# Thermocouple-board.net
KiCad netlist of a schematic drawn in EAGLE
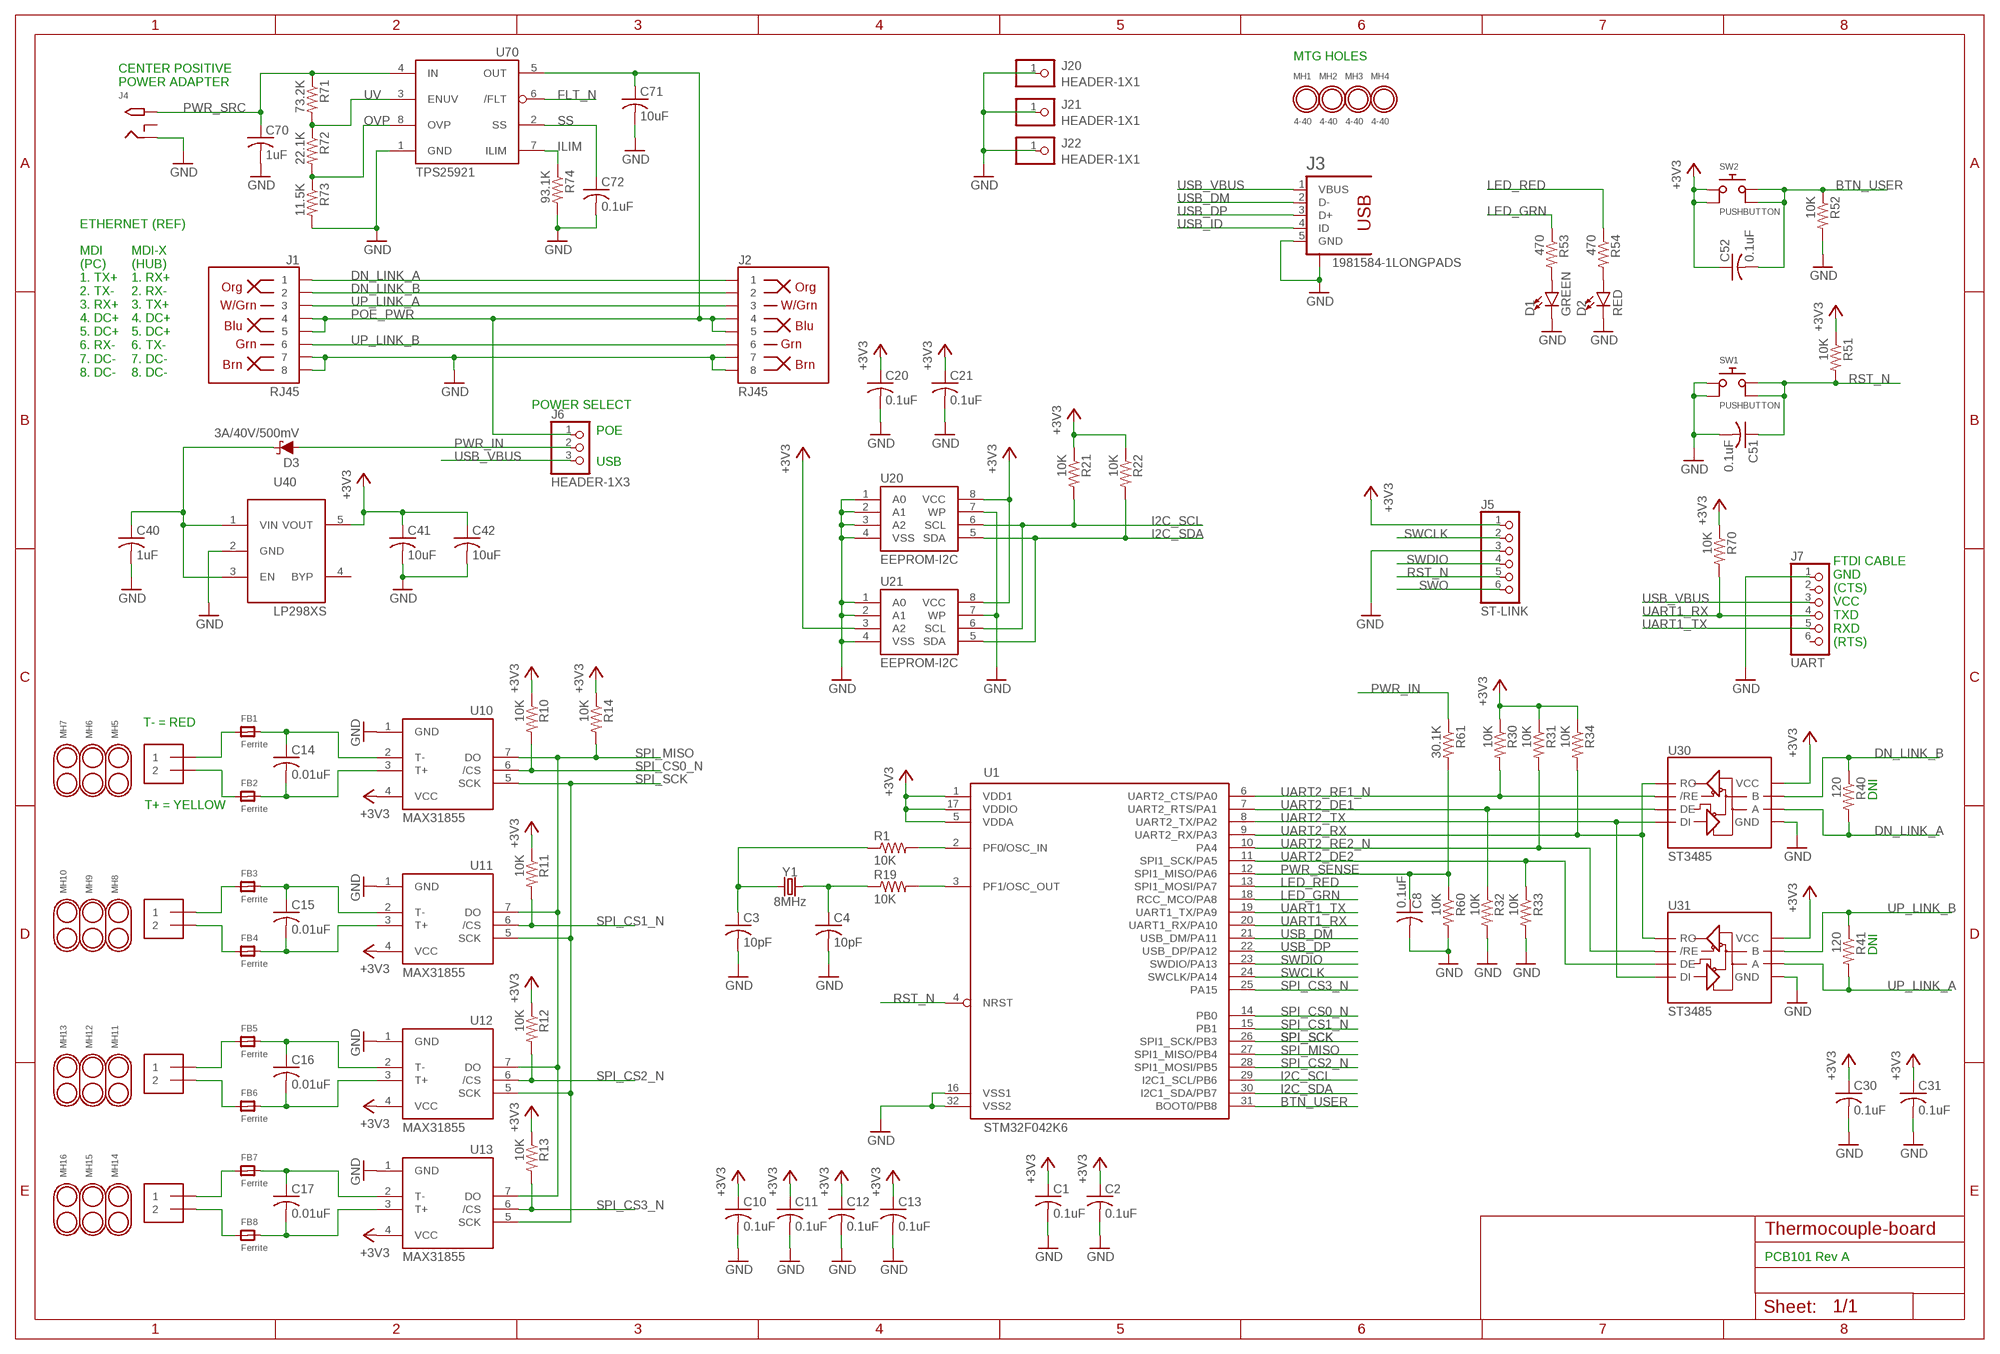
[diagram p0: schematic, sheet 1]

(export (version "E")
  (design (tool "Eeschema 10.0.6"))
  (components
    (comp (ref "C1")
      (value "0.1uF")
      (footprint "eagle-import:C0805K")
      (libsource (lib "eagle-import") (part "adafruit_420_C-USC0805K"))
    )
    (comp (ref "C2")
      (value "0.1uF")
      (footprint "eagle-import:C0805K")
      (libsource (lib "eagle-import") (part "adafruit_420_C-USC0805K"))
    )
    (comp (ref "C3")
      (value "10pF")
      (footprint "eagle-import:C0805K")
      (libsource (lib "eagle-import") (part "adafruit_420_C-USC0805K"))
    )
    (comp (ref "C4")
      (value "10pF")
      (footprint "eagle-import:C0805K")
      (libsource (lib "eagle-import") (part "adafruit_420_C-USC0805K"))
    )
    (comp (ref "C8")
      (value "0.1uF")
      (footprint "eagle-import:C0805K")
      (libsource (lib "eagle-import") (part "adafruit_420_C-USC0805K"))
    )
    (comp (ref "C10")
      (value "0.1uF")
      (footprint "eagle-import:C0805K")
      (libsource (lib "eagle-import") (part "adafruit_420_C-USC0805K"))
    )
    (comp (ref "C11")
      (value "0.1uF")
      (footprint "eagle-import:C0805K")
      (libsource (lib "eagle-import") (part "adafruit_420_C-USC0805K"))
    )
    (comp (ref "C12")
      (value "0.1uF")
      (footprint "eagle-import:C0805K")
      (libsource (lib "eagle-import") (part "adafruit_420_C-USC0805K"))
    )
    (comp (ref "C13")
      (value "0.1uF")
      (footprint "eagle-import:C0805K")
      (libsource (lib "eagle-import") (part "adafruit_420_C-USC0805K"))
    )
    (comp (ref "C14")
      (value "0.01uF")
      (footprint "eagle-import:C0805K")
      (libsource (lib "eagle-import") (part "adafruit_420_C-USC0805K"))
    )
    (comp (ref "C15")
      (value "0.01uF")
      (footprint "eagle-import:C0805K")
      (libsource (lib "eagle-import") (part "adafruit_420_C-USC0805K"))
    )
    (comp (ref "C16")
      (value "0.01uF")
      (footprint "eagle-import:C0805K")
      (libsource (lib "eagle-import") (part "adafruit_420_C-USC0805K"))
    )
    (comp (ref "C17")
      (value "0.01uF")
      (footprint "eagle-import:C0805K")
      (libsource (lib "eagle-import") (part "adafruit_420_C-USC0805K"))
    )
    (comp (ref "C20")
      (value "0.1uF")
      (footprint "eagle-import:C0805K")
      (libsource (lib "eagle-import") (part "adafruit_420_C-USC0805K"))
    )
    (comp (ref "C21")
      (value "0.1uF")
      (footprint "eagle-import:C0805K")
      (libsource (lib "eagle-import") (part "adafruit_420_C-USC0805K"))
    )
    (comp (ref "C30")
      (value "0.1uF")
      (footprint "eagle-import:C0805K")
      (libsource (lib "eagle-import") (part "adafruit_420_C-USC0805K"))
    )
    (comp (ref "C31")
      (value "0.1uF")
      (footprint "eagle-import:C0805K")
      (libsource (lib "eagle-import") (part "adafruit_420_C-USC0805K"))
    )
    (comp (ref "C40")
      (value "1uF")
      (footprint "eagle-import:C0805K")
      (libsource (lib "eagle-import") (part "C-USC0805K"))
    )
    (comp (ref "C41")
      (value "10uF")
      (footprint "eagle-import:C0805K")
      (libsource (lib "eagle-import") (part "C-USC0805K"))
    )
    (comp (ref "C42")
      (value "10uF")
      (footprint "eagle-import:C0805K")
      (libsource (lib "eagle-import") (part "C-USC0805K"))
    )
    (comp (ref "C51")
      (value "0.1uF")
      (footprint "eagle-import:C0805K")
      (libsource (lib "eagle-import") (part "adafruit_420_C-USC0805K"))
    )
    (comp (ref "C52")
      (value "0.1uF")
      (footprint "eagle-import:C0805K")
      (libsource (lib "eagle-import") (part "adafruit_420_C-USC0805K"))
    )
    (comp (ref "C70")
      (value "1uF")
      (footprint "eagle-import:C0805K")
      (libsource (lib "eagle-import") (part "adafruit_420_C-USC0805K"))
    )
    (comp (ref "C71")
      (value "10uF")
      (footprint "eagle-import:C0805K")
      (libsource (lib "eagle-import") (part "adafruit_420_C-USC0805K"))
    )
    (comp (ref "C72")
      (value "0.1uF")
      (footprint "eagle-import:C0805K")
      (libsource (lib "eagle-import") (part "adafruit_420_C-USC0805K"))
    )
    (comp (ref "D1")
      (value "GREEN")
      (footprint "eagle-import:LED-0603")
      (libsource (lib "eagle-import") (part "LED-GREEN0603"))
    )
    (comp (ref "D2")
      (value "RED")
      (footprint "eagle-import:LED-0603")
      (libsource (lib "eagle-import") (part "LED-RED0603"))
    )
    (comp (ref "D3")
      (value "3A/40V/500mV")
      (footprint "eagle-import:SMA-DIODE")
      (libsource (lib "eagle-import") (part "DIODE-SCHOTTKY-B340A"))
    )
    (comp (ref "FB1")
      (value "Ferrite")
      (footprint "eagle-import:_0805")
      (libsource (lib "eagle-import") (part "FERRITE_0805"))
    )
    (comp (ref "FB2")
      (value "Ferrite")
      (footprint "eagle-import:_0805")
      (libsource (lib "eagle-import") (part "FERRITE_0805"))
    )
    (comp (ref "FB3")
      (value "Ferrite")
      (footprint "eagle-import:_0805")
      (libsource (lib "eagle-import") (part "FERRITE_0805"))
    )
    (comp (ref "FB4")
      (value "Ferrite")
      (footprint "eagle-import:_0805")
      (libsource (lib "eagle-import") (part "FERRITE_0805"))
    )
    (comp (ref "FB5")
      (value "Ferrite")
      (footprint "eagle-import:_0805")
      (libsource (lib "eagle-import") (part "FERRITE_0805"))
    )
    (comp (ref "FB6")
      (value "Ferrite")
      (footprint "eagle-import:_0805")
      (libsource (lib "eagle-import") (part "FERRITE_0805"))
    )
    (comp (ref "FB7")
      (value "Ferrite")
      (footprint "eagle-import:_0805")
      (libsource (lib "eagle-import") (part "FERRITE_0805"))
    )
    (comp (ref "FB8")
      (value "Ferrite")
      (footprint "eagle-import:_0805")
      (libsource (lib "eagle-import") (part "FERRITE_0805"))
    )
    (comp (ref "J1")
      (value "RJ45")
      (footprint "eagle-import:RJ45-8")
      (libsource (lib "eagle-import") (part "RJ45-8"))
    )
    (comp (ref "J2")
      (value "RJ45")
      (footprint "eagle-import:RJ45-8")
      (libsource (lib "eagle-import") (part "RJ45-8"))
    )
    (comp (ref "J3")
      (value "1981584-1LONGPADS")
      (footprint "eagle-import:1981584-1-LONG")
      (libsource (lib "eagle-import") (part "1981584-1LONGPADS"))
    )
    (comp (ref "J4")
      (value "2.1MMJACKTHM")
      (footprint "eagle-import:PJ-102A")
      (libsource (lib "eagle-import") (part "2.1MMJACKTHM"))
    )
    (comp (ref "J5")
      (value "ST-LINK")
      (footprint "eagle-import:1X06_OVAL")
      (libsource (lib "eagle-import") (part "HEADER-1X6"))
    )
    (comp (ref "J6")
      (value "HEADER-1X3")
      (footprint "eagle-import:1X03_OVAL")
      (libsource (lib "eagle-import") (part "HEADER-1X3"))
    )
    (comp (ref "J7")
      (value "UART")
      (footprint "eagle-import:1X06_OVAL")
      (libsource (lib "eagle-import") (part "HEADER-1X6"))
    )
    (comp (ref "J10")
      (value "1X2-3.5MM")
      (footprint "eagle-import:1X2-3.5MM")
      (libsource (lib "eagle-import") (part "1X2-3.5MM"))
    )
    (comp (ref "J11")
      (value "1X2-3.5MM")
      (footprint "eagle-import:1X2-3.5MM")
      (libsource (lib "eagle-import") (part "1X2-3.5MM"))
    )
    (comp (ref "J12")
      (value "1X2-3.5MM")
      (footprint "eagle-import:1X2-3.5MM")
      (libsource (lib "eagle-import") (part "1X2-3.5MM"))
    )
    (comp (ref "J13")
      (value "1X2-3.5MM")
      (footprint "eagle-import:1X2-3.5MM")
      (libsource (lib "eagle-import") (part "1X2-3.5MM"))
    )
    (comp (ref "J20")
      (value "HEADER-1X1")
      (footprint "eagle-import:1X01_OVAL")
      (libsource (lib "eagle-import") (part "HEADER-1X1"))
    )
    (comp (ref "J21")
      (value "HEADER-1X1")
      (footprint "eagle-import:1X01_OVAL")
      (libsource (lib "eagle-import") (part "HEADER-1X1"))
    )
    (comp (ref "J22")
      (value "HEADER-1X1")
      (footprint "eagle-import:1X01_OVAL")
      (libsource (lib "eagle-import") (part "HEADER-1X1"))
    )
    (comp (ref "MH1")
      (value "4-40")
      (footprint "eagle-import:MTG_HOLE_C280_H125")
      (libsource (lib "eagle-import") (part "MTG_HOLE_4-40"))
    )
    (comp (ref "MH2")
      (value "4-40")
      (footprint "eagle-import:MTG_HOLE_C280_H125")
      (libsource (lib "eagle-import") (part "MTG_HOLE_4-40"))
    )
    (comp (ref "MH3")
      (value "4-40")
      (footprint "eagle-import:MTG_HOLE_C280_H125")
      (libsource (lib "eagle-import") (part "MTG_HOLE_4-40"))
    )
    (comp (ref "MH4")
      (value "4-40")
      (footprint "eagle-import:MTG_HOLE_C280_H125")
      (libsource (lib "eagle-import") (part "MTG_HOLE_4-40"))
    )
    (comp (ref "MH5")
      (value "HOLD_DOWN")
      (footprint "eagle-import:HOLD_DOWN")
      (libsource (lib "eagle-import") (part "HOLD_DOWN"))
    )
    (comp (ref "MH6")
      (value "HOLD_DOWN")
      (footprint "eagle-import:HOLD_DOWN")
      (libsource (lib "eagle-import") (part "HOLD_DOWN"))
    )
    (comp (ref "MH7")
      (value "HOLD_DOWN")
      (footprint "eagle-import:HOLD_DOWN")
      (libsource (lib "eagle-import") (part "HOLD_DOWN"))
    )
    (comp (ref "MH8")
      (value "HOLD_DOWN")
      (footprint "eagle-import:HOLD_DOWN")
      (libsource (lib "eagle-import") (part "HOLD_DOWN"))
    )
    (comp (ref "MH9")
      (value "HOLD_DOWN")
      (footprint "eagle-import:HOLD_DOWN")
      (libsource (lib "eagle-import") (part "HOLD_DOWN"))
    )
    (comp (ref "MH10")
      (value "HOLD_DOWN")
      (footprint "eagle-import:HOLD_DOWN")
      (libsource (lib "eagle-import") (part "HOLD_DOWN"))
    )
    (comp (ref "MH11")
      (value "HOLD_DOWN")
      (footprint "eagle-import:HOLD_DOWN")
      (libsource (lib "eagle-import") (part "HOLD_DOWN"))
    )
    (comp (ref "MH12")
      (value "HOLD_DOWN")
      (footprint "eagle-import:HOLD_DOWN")
      (libsource (lib "eagle-import") (part "HOLD_DOWN"))
    )
    (comp (ref "MH13")
      (value "HOLD_DOWN")
      (footprint "eagle-import:HOLD_DOWN")
      (libsource (lib "eagle-import") (part "HOLD_DOWN"))
    )
    (comp (ref "MH14")
      (value "HOLD_DOWN")
      (footprint "eagle-import:HOLD_DOWN")
      (libsource (lib "eagle-import") (part "HOLD_DOWN"))
    )
    (comp (ref "MH15")
      (value "HOLD_DOWN")
      (footprint "eagle-import:HOLD_DOWN")
      (libsource (lib "eagle-import") (part "HOLD_DOWN"))
    )
    (comp (ref "MH16")
      (value "HOLD_DOWN")
      (footprint "eagle-import:HOLD_DOWN")
      (libsource (lib "eagle-import") (part "HOLD_DOWN"))
    )
    (comp (ref "R1")
      (value "10K")
      (footprint "eagle-import:R0805")
      (libsource (lib "eagle-import") (part "R-US_R0805"))
    )
    (comp (ref "R10")
      (value "10K")
      (footprint "eagle-import:R0805")
      (libsource (lib "eagle-import") (part "R-US_R0805"))
    )
    (comp (ref "R11")
      (value "10K")
      (footprint "eagle-import:R0805")
      (libsource (lib "eagle-import") (part "R-US_R0805"))
    )
    (comp (ref "R12")
      (value "10K")
      (footprint "eagle-import:R0805")
      (libsource (lib "eagle-import") (part "R-US_R0805"))
    )
    (comp (ref "R13")
      (value "10K")
      (footprint "eagle-import:R0805")
      (libsource (lib "eagle-import") (part "R-US_R0805"))
    )
    (comp (ref "R14")
      (value "10K")
      (footprint "eagle-import:R0805")
      (libsource (lib "eagle-import") (part "R-US_R0805"))
    )
    (comp (ref "R19")
      (value "10K")
      (footprint "eagle-import:R0805")
      (libsource (lib "eagle-import") (part "R-US_R0805"))
    )
    (comp (ref "R21")
      (value "10K")
      (footprint "eagle-import:R0805")
      (libsource (lib "eagle-import") (part "R-US_R0805"))
    )
    (comp (ref "R22")
      (value "10K")
      (footprint "eagle-import:R0805")
      (libsource (lib "eagle-import") (part "R-US_R0805"))
    )
    (comp (ref "R30")
      (value "10K")
      (footprint "eagle-import:R0805")
      (libsource (lib "eagle-import") (part "R-US_R0805"))
    )
    (comp (ref "R31")
      (value "10K")
      (footprint "eagle-import:R0805")
      (libsource (lib "eagle-import") (part "R-US_R0805"))
    )
    (comp (ref "R32")
      (value "10K")
      (footprint "eagle-import:R0805")
      (libsource (lib "eagle-import") (part "R-US_R0805"))
    )
    (comp (ref "R33")
      (value "10K")
      (footprint "eagle-import:R0805")
      (libsource (lib "eagle-import") (part "R-US_R0805"))
    )
    (comp (ref "R34")
      (value "10K")
      (footprint "eagle-import:R0805")
      (libsource (lib "eagle-import") (part "R-US_R0805"))
    )
    (comp (ref "R40")
      (value "120")
      (footprint "eagle-import:R0805")
      (libsource (lib "eagle-import") (part "R-US_R0805"))
    )
    (comp (ref "R41")
      (value "120")
      (footprint "eagle-import:R0805")
      (libsource (lib "eagle-import") (part "R-US_R0805"))
    )
    (comp (ref "R51")
      (value "10K")
      (footprint "eagle-import:R0805")
      (libsource (lib "eagle-import") (part "R-US_R0805"))
    )
    (comp (ref "R52")
      (value "10K")
      (footprint "eagle-import:R0805")
      (libsource (lib "eagle-import") (part "R-US_R0805"))
    )
    (comp (ref "R53")
      (value "470")
      (footprint "eagle-import:R0805")
      (libsource (lib "eagle-import") (part "R-US_R0805"))
    )
    (comp (ref "R54")
      (value "470")
      (footprint "eagle-import:R0805")
      (libsource (lib "eagle-import") (part "R-US_R0805"))
    )
    (comp (ref "R60")
      (value "10K")
      (footprint "eagle-import:R0805")
      (libsource (lib "eagle-import") (part "R-US_R0805"))
    )
    (comp (ref "R61")
      (value "30.1K")
      (footprint "eagle-import:R0805")
      (libsource (lib "eagle-import") (part "R-US_R0805"))
    )
    (comp (ref "R70")
      (value "10K")
      (footprint "eagle-import:R0805")
      (libsource (lib "eagle-import") (part "R-US_R0805"))
    )
    (comp (ref "R71")
      (value "73.2K")
      (footprint "eagle-import:R0805")
      (libsource (lib "eagle-import") (part "R-US_R0805"))
    )
    (comp (ref "R72")
      (value "22.1K")
      (footprint "eagle-import:R0805")
      (libsource (lib "eagle-import") (part "R-US_R0805"))
    )
    (comp (ref "R73")
      (value "11.5K")
      (footprint "eagle-import:R0805")
      (libsource (lib "eagle-import") (part "R-US_R0805"))
    )
    (comp (ref "R74")
      (value "93.1K")
      (footprint "eagle-import:R0805")
      (libsource (lib "eagle-import") (part "R-US_R0805"))
    )
    (comp (ref "SW1")
      (value "PUSHBUTTON")
      (footprint "eagle-import:PUSHBUTTON_6X6MM")
      (libsource (lib "eagle-import") (part "PUSHBUTTON"))
    )
    (comp (ref "SW2")
      (value "PUSHBUTTON")
      (footprint "eagle-import:PUSHBUTTON_6X6MM")
      (libsource (lib "eagle-import") (part "PUSHBUTTON"))
    )
    (comp (ref "U1")
      (value "STM32F042K6")
      (footprint "eagle-import:TQFP32-0.8MM")
      (libsource (lib "eagle-import") (part "STM32F042K4_V02"))
    )
    (comp (ref "U10")
      (value "MAX31855")
      (footprint "eagle-import:SO08")
      (libsource (lib "eagle-import") (part "MAX31855"))
    )
    (comp (ref "U11")
      (value "MAX31855")
      (footprint "eagle-import:SO08")
      (libsource (lib "eagle-import") (part "MAX31855"))
    )
    (comp (ref "U12")
      (value "MAX31855")
      (footprint "eagle-import:SO08")
      (libsource (lib "eagle-import") (part "MAX31855"))
    )
    (comp (ref "U13")
      (value "MAX31855")
      (footprint "eagle-import:SO08")
      (libsource (lib "eagle-import") (part "MAX31855"))
    )
    (comp (ref "U20")
      (value "EEPROM-I2C")
      (footprint "eagle-import:SO08")
      (libsource (lib "eagle-import") (part "EEPROM-I2C"))
    )
    (comp (ref "U21")
      (value "EEPROM-I2C")
      (footprint "eagle-import:SO08")
      (libsource (lib "eagle-import") (part "EEPROM-I2C"))
    )
    (comp (ref "U30")
      (value "ST3485")
      (footprint "eagle-import:SO08")
      (libsource (lib "eagle-import") (part "RS485SOIC"))
    )
    (comp (ref "U31")
      (value "ST3485")
      (footprint "eagle-import:SO08")
      (libsource (lib "eagle-import") (part "RS485SOIC"))
    )
    (comp (ref "U40")
      (value "LP298XS")
      (footprint "eagle-import:SOT23-5L")
      (libsource (lib "eagle-import") (part "LP298XS"))
    )
    (comp (ref "U70")
      (value "TPS25921")
      (footprint "eagle-import:SO08")
      (libsource (lib "eagle-import") (part "TPS25921"))
    )
    (comp (ref "Y1")
      (value "8MHz")
      (footprint "eagle-import:HC49UP")
      (libsource (lib "eagle-import") (part "CRYSTAL-8MHZSMD-HC49UP"))
    )
  )
  (nets
    (net (code "1") (name "+3V3") (class "Default")
      (node (ref "C1") (pin "1") (pinfunction "1_1") (pintype "passive"))
      (node (ref "C10") (pin "1") (pinfunction "1_1") (pintype "passive"))
      (node (ref "C11") (pin "1") (pinfunction "1_1") (pintype "passive"))
      (node (ref "C12") (pin "1") (pinfunction "1_1") (pintype "passive"))
      (node (ref "C13") (pin "1") (pinfunction "1_1") (pintype "passive"))
      (node (ref "C2") (pin "1") (pinfunction "1_1") (pintype "passive"))
      (node (ref "C20") (pin "1") (pinfunction "1_1") (pintype "passive"))
      (node (ref "C21") (pin "1") (pinfunction "1_1") (pintype "passive"))
      (node (ref "C30") (pin "1") (pinfunction "1_1") (pintype "passive"))
      (node (ref "C31") (pin "1") (pinfunction "1_1") (pintype "passive"))
      (node (ref "C41") (pin "1") (pinfunction "1_1") (pintype "passive"))
      (node (ref "C42") (pin "1") (pinfunction "1_1") (pintype "passive"))
      (node (ref "C52") (pin "1") (pinfunction "1_1") (pintype "passive"))
      (node (ref "J5") (pin "1") (pinfunction "1_1") (pintype "passive"))
      (node (ref "R10") (pin "1") (pinfunction "1_1") (pintype "passive"))
      (node (ref "R11") (pin "1") (pinfunction "1_1") (pintype "passive"))
      (node (ref "R12") (pin "1") (pinfunction "1_1") (pintype "passive"))
      (node (ref "R13") (pin "1") (pinfunction "1_1") (pintype "passive"))
      (node (ref "R14") (pin "1") (pinfunction "1_1") (pintype "passive"))
      (node (ref "R21") (pin "1") (pinfunction "1_1") (pintype "passive"))
      (node (ref "R22") (pin "1") (pinfunction "1_1") (pintype "passive"))
      (node (ref "R30") (pin "1") (pinfunction "1_1") (pintype "passive"))
      (node (ref "R31") (pin "1") (pinfunction "1_1") (pintype "passive"))
      (node (ref "R34") (pin "1") (pinfunction "1_1") (pintype "passive"))
      (node (ref "R51") (pin "1") (pinfunction "1_1") (pintype "passive"))
      (node (ref "R70") (pin "1") (pinfunction "1_1") (pintype "passive"))
      (node (ref "SW2") (pin "1") (pinfunction "P$1_1") (pintype "passive"))
      (node (ref "SW2") (pin "2") (pinfunction "P$2_2") (pintype "passive"))
      (node (ref "U1") (pin "1") (pinfunction "VDD1_1") (pintype "bidirectional"))
      (node (ref "U1") (pin "17") (pinfunction "VDDIO_17") (pintype "bidirectional"))
      (node (ref "U1") (pin "5") (pinfunction "VDDA_5") (pintype "bidirectional"))
      (node (ref "U10") (pin "4") (pinfunction "VCC_4") (pintype "power_in"))
      (node (ref "U11") (pin "4") (pinfunction "VCC_4") (pintype "power_in"))
      (node (ref "U12") (pin "4") (pinfunction "VCC_4") (pintype "power_in"))
      (node (ref "U13") (pin "4") (pinfunction "VCC_4") (pintype "power_in"))
      (node (ref "U20") (pin "8") (pinfunction "VCC_8") (pintype "power_in"))
      (node (ref "U21") (pin "3") (pinfunction "A2_3") (pintype "bidirectional"))
      (node (ref "U21") (pin "8") (pinfunction "VCC_8") (pintype "power_in"))
      (node (ref "U30") (pin "8") (pinfunction "VCC_8") (pintype "bidirectional"))
      (node (ref "U31") (pin "8") (pinfunction "VCC_8") (pintype "bidirectional"))
      (node (ref "U40") (pin "5") (pinfunction "VOUT_5") (pintype "bidirectional"))
    )
    (net (code "2") (name "/BTN_USER") (class "Default")
      (node (ref "C52") (pin "2") (pinfunction "2_2") (pintype "passive"))
      (node (ref "R52") (pin "1") (pinfunction "1_1") (pintype "passive"))
      (node (ref "SW2") (pin "3") (pinfunction "P$3_3") (pintype "passive"))
      (node (ref "SW2") (pin "4") (pinfunction "P$4_4") (pintype "passive"))
      (node (ref "U1") (pin "31") (pinfunction "BOOT0/PB8_31") (pintype "bidirectional"))
    )
    (net (code "3") (name "/DN_LINK_A") (class "Default")
      (node (ref "J1") (pin "1") (pinfunction "1_1") (pintype "bidirectional"))
      (node (ref "J2") (pin "1") (pinfunction "1_1") (pintype "bidirectional"))
      (node (ref "R40") (pin "2") (pinfunction "2_2") (pintype "passive"))
      (node (ref "U30") (pin "6") (pinfunction "A_6") (pintype "bidirectional"))
    )
    (net (code "4") (name "/DN_LINK_B") (class "Default")
      (node (ref "J1") (pin "2") (pinfunction "2_2") (pintype "bidirectional"))
      (node (ref "J2") (pin "2") (pinfunction "2_2") (pintype "bidirectional"))
      (node (ref "R40") (pin "1") (pinfunction "1_1") (pintype "passive"))
      (node (ref "U30") (pin "7") (pinfunction "B_7") (pintype "bidirectional"))
    )
    (net (code "5") (name "/FLT_N") (class "Default")
      (node (ref "U70") (pin "6") (pinfunction "/FLT_6") (pintype "output"))
    )
    (net (code "6") (name "/I2C_SCL") (class "Default")
      (node (ref "R21") (pin "2") (pinfunction "2_2") (pintype "passive"))
      (node (ref "U1") (pin "29") (pinfunction "I2C1_SCL/PB6_29") (pintype "bidirectional"))
      (node (ref "U20") (pin "6") (pinfunction "SCL_6") (pintype "bidirectional"))
      (node (ref "U21") (pin "6") (pinfunction "SCL_6") (pintype "bidirectional"))
    )
    (net (code "7") (name "/I2C_SDA") (class "Default")
      (node (ref "R22") (pin "2") (pinfunction "2_2") (pintype "passive"))
      (node (ref "U1") (pin "30") (pinfunction "I2C1_SDA/PB7_30") (pintype "bidirectional"))
      (node (ref "U20") (pin "5") (pinfunction "SDA_5") (pintype "bidirectional"))
      (node (ref "U21") (pin "5") (pinfunction "SDA_5") (pintype "bidirectional"))
    )
    (net (code "8") (name "/ILIM") (class "Default")
      (node (ref "R74") (pin "1") (pinfunction "1_1") (pintype "passive"))
      (node (ref "U70") (pin "7") (pinfunction "ILIM_7") (pintype "input"))
    )
    (net (code "9") (name "/LED_GRN") (class "Default")
      (node (ref "R53") (pin "1") (pinfunction "1_1") (pintype "passive"))
      (node (ref "U1") (pin "18") (pinfunction "RCC_MCO/PA8_18") (pintype "bidirectional"))
    )
    (net (code "10") (name "/LED_RED") (class "Default")
      (node (ref "R54") (pin "1") (pinfunction "1_1") (pintype "passive"))
      (node (ref "U1") (pin "13") (pinfunction "SPI1_MOSI/PA7_13") (pintype "bidirectional"))
    )
    (net (code "11") (name "/OVP") (class "Default")
      (node (ref "R72") (pin "2") (pinfunction "2_2") (pintype "passive"))
      (node (ref "R73") (pin "1") (pinfunction "1_1") (pintype "passive"))
      (node (ref "U70") (pin "8") (pinfunction "OVP_8") (pintype "input"))
    )
    (net (code "12") (name "/POE_PWR") (class "Default")
      (node (ref "C71") (pin "1") (pinfunction "1_1") (pintype "passive"))
      (node (ref "J1") (pin "4") (pinfunction "4_4") (pintype "bidirectional"))
      (node (ref "J1") (pin "5") (pinfunction "5_5") (pintype "bidirectional"))
      (node (ref "J2") (pin "4") (pinfunction "4_4") (pintype "bidirectional"))
      (node (ref "J2") (pin "5") (pinfunction "5_5") (pintype "bidirectional"))
      (node (ref "J6") (pin "1") (pinfunction "1_1") (pintype "passive"))
      (node (ref "U70") (pin "5") (pinfunction "OUT_5") (pintype "output"))
    )
    (net (code "13") (name "/PWR_IN") (class "Default")
      (node (ref "D3") (pin "A") (pinfunction "A_A") (pintype "passive"))
      (node (ref "J6") (pin "2") (pinfunction "2_2") (pintype "passive"))
      (node (ref "R61") (pin "1") (pinfunction "1_1") (pintype "passive"))
    )
    (net (code "14") (name "/PWR_SENSE") (class "Default")
      (node (ref "C8") (pin "1") (pinfunction "1_1") (pintype "passive"))
      (node (ref "R60") (pin "1") (pinfunction "1_1") (pintype "passive"))
      (node (ref "R61") (pin "2") (pinfunction "2_2") (pintype "passive"))
      (node (ref "U1") (pin "12") (pinfunction "SPI1_MISO/PA6_12") (pintype "bidirectional"))
    )
    (net (code "15") (name "/PWR_SRC") (class "Default")
      (node (ref "C70") (pin "1") (pinfunction "1_1") (pintype "passive"))
      (node (ref "J4") (pin "TIP") (pinfunction "TIP_TIP") (pintype "bidirectional"))
      (node (ref "R71") (pin "1") (pinfunction "1_1") (pintype "passive"))
      (node (ref "U70") (pin "4") (pinfunction "IN_4") (pintype "input"))
    )
    (net (code "16") (name "/RST_N") (class "Default")
      (node (ref "C51") (pin "1") (pinfunction "1_1") (pintype "passive"))
      (node (ref "J5") (pin "5") (pinfunction "5_5") (pintype "passive"))
      (node (ref "R51") (pin "2") (pinfunction "2_2") (pintype "passive"))
      (node (ref "SW1") (pin "3") (pinfunction "P$3_3") (pintype "passive"))
      (node (ref "SW1") (pin "4") (pinfunction "P$4_4") (pintype "passive"))
      (node (ref "U1") (pin "4") (pinfunction "NRST_4") (pintype "bidirectional"))
    )
    (net (code "17") (name "/SPI_CS0_N") (class "Default")
      (node (ref "R10") (pin "2") (pinfunction "2_2") (pintype "passive"))
      (node (ref "U1") (pin "14") (pinfunction "PB0_14") (pintype "bidirectional"))
      (node (ref "U10") (pin "6") (pinfunction "/CS_6") (pintype "input"))
    )
    (net (code "18") (name "/SPI_CS1_N") (class "Default")
      (node (ref "R11") (pin "2") (pinfunction "2_2") (pintype "passive"))
      (node (ref "U1") (pin "15") (pinfunction "PB1_15") (pintype "bidirectional"))
      (node (ref "U11") (pin "6") (pinfunction "/CS_6") (pintype "input"))
    )
    (net (code "19") (name "/SPI_CS2_N") (class "Default")
      (node (ref "R12") (pin "2") (pinfunction "2_2") (pintype "passive"))
      (node (ref "U1") (pin "28") (pinfunction "SPI1_MOSI/PB5_28") (pintype "bidirectional"))
      (node (ref "U12") (pin "6") (pinfunction "/CS_6") (pintype "input"))
    )
    (net (code "20") (name "/SPI_CS3_N") (class "Default")
      (node (ref "R13") (pin "2") (pinfunction "2_2") (pintype "passive"))
      (node (ref "U1") (pin "25") (pinfunction "PA15_25") (pintype "bidirectional"))
      (node (ref "U13") (pin "6") (pinfunction "/CS_6") (pintype "input"))
    )
    (net (code "21") (name "/SPI_MISO") (class "Default")
      (node (ref "R14") (pin "2") (pinfunction "2_2") (pintype "passive"))
      (node (ref "U1") (pin "27") (pinfunction "SPI1_MISO/PB4_27") (pintype "bidirectional"))
      (node (ref "U10") (pin "7") (pinfunction "DO_7") (pintype "output"))
      (node (ref "U11") (pin "7") (pinfunction "DO_7") (pintype "output"))
      (node (ref "U12") (pin "7") (pinfunction "DO_7") (pintype "output"))
      (node (ref "U13") (pin "7") (pinfunction "DO_7") (pintype "output"))
    )
    (net (code "22") (name "/SPI_SCK") (class "Default")
      (node (ref "U1") (pin "26") (pinfunction "SPI1_SCK/PB3_26") (pintype "bidirectional"))
      (node (ref "U10") (pin "5") (pinfunction "SCK_5") (pintype "input"))
      (node (ref "U11") (pin "5") (pinfunction "SCK_5") (pintype "input"))
      (node (ref "U12") (pin "5") (pinfunction "SCK_5") (pintype "input"))
      (node (ref "U13") (pin "5") (pinfunction "SCK_5") (pintype "input"))
    )
    (net (code "23") (name "/SS") (class "Default")
      (node (ref "C72") (pin "1") (pinfunction "1_1") (pintype "passive"))
      (node (ref "U70") (pin "2") (pinfunction "SS_2") (pintype "bidirectional"))
    )
    (net (code "24") (name "/SWCLK") (class "Default")
      (node (ref "J5") (pin "2") (pinfunction "2_2") (pintype "passive"))
      (node (ref "U1") (pin "24") (pinfunction "SWCLK/PA14_24") (pintype "bidirectional"))
    )
    (net (code "25") (name "/SWDIO") (class "Default")
      (node (ref "J5") (pin "4") (pinfunction "4_4") (pintype "passive"))
      (node (ref "U1") (pin "23") (pinfunction "SWDIO/PA13_23") (pintype "bidirectional"))
    )
    (net (code "26") (name "/SWO") (class "Default")
      (node (ref "J5") (pin "6") (pinfunction "6_6") (pintype "passive"))
    )
    (net (code "27") (name "/UART1_RX") (class "Default")
      (node (ref "J7") (pin "4") (pinfunction "4_4") (pintype "passive"))
      (node (ref "R70") (pin "2") (pinfunction "2_2") (pintype "passive"))
      (node (ref "U1") (pin "20") (pinfunction "UART1_RX/PA10_20") (pintype "bidirectional"))
    )
    (net (code "28") (name "/UART1_TX") (class "Default")
      (node (ref "J7") (pin "5") (pinfunction "5_5") (pintype "passive"))
      (node (ref "U1") (pin "19") (pinfunction "UART1_TX/PA9_19") (pintype "bidirectional"))
    )
    (net (code "29") (name "/UART2_DE1") (class "Default")
      (node (ref "R32") (pin "1") (pinfunction "1_1") (pintype "passive"))
      (node (ref "U1") (pin "7") (pinfunction "UART2_RTS/PA1_7") (pintype "bidirectional"))
      (node (ref "U30") (pin "3") (pinfunction "DE_3") (pintype "bidirectional"))
    )
    (net (code "30") (name "/UART2_DE2") (class "Default")
      (node (ref "R33") (pin "1") (pinfunction "1_1") (pintype "passive"))
      (node (ref "U1") (pin "11") (pinfunction "SPI1_SCK/PA5_11") (pintype "bidirectional"))
      (node (ref "U31") (pin "3") (pinfunction "DE_3") (pintype "bidirectional"))
    )
    (net (code "31") (name "/UART2_RE1_N") (class "Default")
      (node (ref "R30") (pin "2") (pinfunction "2_2") (pintype "passive"))
      (node (ref "U1") (pin "6") (pinfunction "UART2_CTS/PA0_6") (pintype "bidirectional"))
      (node (ref "U30") (pin "2") (pinfunction "/RE_2") (pintype "bidirectional"))
    )
    (net (code "32") (name "/UART2_RE2_N") (class "Default")
      (node (ref "R31") (pin "2") (pinfunction "2_2") (pintype "passive"))
      (node (ref "U1") (pin "10") (pinfunction "PA4_10") (pintype "bidirectional"))
      (node (ref "U31") (pin "2") (pinfunction "/RE_2") (pintype "bidirectional"))
    )
    (net (code "33") (name "/UART2_RX") (class "Default")
      (node (ref "R34") (pin "2") (pinfunction "2_2") (pintype "passive"))
      (node (ref "U1") (pin "9") (pinfunction "UART2_RX/PA3_9") (pintype "bidirectional"))
      (node (ref "U30") (pin "1") (pinfunction "RO_1") (pintype "bidirectional"))
      (node (ref "U31") (pin "1") (pinfunction "RO_1") (pintype "bidirectional"))
    )
    (net (code "34") (name "/UART2_TX") (class "Default")
      (node (ref "U1") (pin "8") (pinfunction "UART2_TX/PA2_8") (pintype "bidirectional"))
      (node (ref "U30") (pin "4") (pinfunction "DI_4") (pintype "bidirectional"))
      (node (ref "U31") (pin "4") (pinfunction "DI_4") (pintype "bidirectional"))
    )
    (net (code "35") (name "/UP_LINK_A") (class "Default")
      (node (ref "J1") (pin "3") (pinfunction "3_3") (pintype "bidirectional"))
      (node (ref "J2") (pin "3") (pinfunction "3_3") (pintype "bidirectional"))
      (node (ref "R41") (pin "2") (pinfunction "2_2") (pintype "passive"))
      (node (ref "U31") (pin "6") (pinfunction "A_6") (pintype "bidirectional"))
    )
    (net (code "36") (name "/UP_LINK_B") (class "Default")
      (node (ref "J1") (pin "6") (pinfunction "6_6") (pintype "bidirectional"))
      (node (ref "J2") (pin "6") (pinfunction "6_6") (pintype "bidirectional"))
      (node (ref "R41") (pin "1") (pinfunction "1_1") (pintype "passive"))
      (node (ref "U31") (pin "7") (pinfunction "B_7") (pintype "bidirectional"))
    )
    (net (code "37") (name "/USB_DM") (class "Default")
      (node (ref "J3") (pin "2") (pinfunction "D-_2") (pintype "passive"))
      (node (ref "U1") (pin "21") (pinfunction "USB_DM/PA11_21") (pintype "bidirectional"))
    )
    (net (code "38") (name "/USB_DP") (class "Default")
      (node (ref "J3") (pin "3") (pinfunction "D+_3") (pintype "passive"))
      (node (ref "U1") (pin "22") (pinfunction "USB_DP/PA12_22") (pintype "bidirectional"))
    )
    (net (code "39") (name "/USB_ID") (class "Default")
      (node (ref "J3") (pin "4") (pinfunction "ID_4") (pintype "passive"))
    )
    (net (code "40") (name "/USB_VBUS") (class "Default")
      (node (ref "J3") (pin "1") (pinfunction "VBUS_1") (pintype "passive"))
      (node (ref "J6") (pin "3") (pinfunction "3_3") (pintype "passive"))
      (node (ref "J7") (pin "3") (pinfunction "3_3") (pintype "passive"))
    )
    (net (code "41") (name "/UV") (class "Default")
      (node (ref "R71") (pin "2") (pinfunction "2_2") (pintype "passive"))
      (node (ref "R72") (pin "1") (pinfunction "1_1") (pintype "passive"))
      (node (ref "U70") (pin "3") (pinfunction "ENUV_3") (pintype "input"))
    )
    (net (code "42") (name "GND") (class "Default")
      (node (ref "C1") (pin "2") (pinfunction "2_2") (pintype "passive"))
      (node (ref "C10") (pin "2") (pinfunction "2_2") (pintype "passive"))
      (node (ref "C11") (pin "2") (pinfunction "2_2") (pintype "passive"))
      (node (ref "C12") (pin "2") (pinfunction "2_2") (pintype "passive"))
      (node (ref "C13") (pin "2") (pinfunction "2_2") (pintype "passive"))
      (node (ref "C2") (pin "2") (pinfunction "2_2") (pintype "passive"))
      (node (ref "C20") (pin "2") (pinfunction "2_2") (pintype "passive"))
      (node (ref "C21") (pin "2") (pinfunction "2_2") (pintype "passive"))
      (node (ref "C3") (pin "2") (pinfunction "2_2") (pintype "passive"))
      (node (ref "C30") (pin "2") (pinfunction "2_2") (pintype "passive"))
      (node (ref "C31") (pin "2") (pinfunction "2_2") (pintype "passive"))
      (node (ref "C4") (pin "2") (pinfunction "2_2") (pintype "passive"))
      (node (ref "C40") (pin "2") (pinfunction "2_2") (pintype "passive"))
      (node (ref "C41") (pin "2") (pinfunction "2_2") (pintype "passive"))
      (node (ref "C42") (pin "2") (pinfunction "2_2") (pintype "passive"))
      (node (ref "C51") (pin "2") (pinfunction "2_2") (pintype "passive"))
      (node (ref "C70") (pin "2") (pinfunction "2_2") (pintype "passive"))
      (node (ref "C71") (pin "2") (pinfunction "2_2") (pintype "passive"))
      (node (ref "C72") (pin "2") (pinfunction "2_2") (pintype "passive"))
      (node (ref "C8") (pin "2") (pinfunction "2_2") (pintype "passive"))
      (node (ref "D1") (pin "C") (pinfunction "C_C") (pintype "passive"))
      (node (ref "D2") (pin "C") (pinfunction "C_C") (pintype "passive"))
      (node (ref "J1") (pin "7") (pinfunction "7_7") (pintype "bidirectional"))
      (node (ref "J1") (pin "8") (pinfunction "8_8") (pintype "bidirectional"))
      (node (ref "J2") (pin "7") (pinfunction "7_7") (pintype "bidirectional"))
      (node (ref "J2") (pin "8") (pinfunction "8_8") (pintype "bidirectional"))
      (node (ref "J20") (pin "1") (pinfunction "1_1") (pintype "passive"))
      (node (ref "J21") (pin "1") (pinfunction "1_1") (pintype "passive"))
      (node (ref "J22") (pin "1") (pinfunction "1_1") (pintype "passive"))
      (node (ref "J3") (pin "5") (pinfunction "GND_5") (pintype "passive"))
      (node (ref "J3") (pin "S1") (pinfunction "S1_S1") (pintype "passive"))
      (node (ref "J4") (pin "RING") (pinfunction "RING_RING") (pintype "bidirectional"))
      (node (ref "J5") (pin "3") (pinfunction "3_3") (pintype "passive"))
      (node (ref "J7") (pin "1") (pinfunction "1_1") (pintype "passive"))
      (node (ref "R32") (pin "2") (pinfunction "2_2") (pintype "passive"))
      (node (ref "R33") (pin "2") (pinfunction "2_2") (pintype "passive"))
      (node (ref "R52") (pin "2") (pinfunction "2_2") (pintype "passive"))
      (node (ref "R60") (pin "2") (pinfunction "2_2") (pintype "passive"))
      (node (ref "R73") (pin "2") (pinfunction "2_2") (pintype "passive"))
      (node (ref "R74") (pin "2") (pinfunction "2_2") (pintype "passive"))
      (node (ref "SW1") (pin "1") (pinfunction "P$1_1") (pintype "passive"))
      (node (ref "SW1") (pin "2") (pinfunction "P$2_2") (pintype "passive"))
      (node (ref "U1") (pin "16") (pinfunction "VSS1_16") (pintype "bidirectional"))
      (node (ref "U1") (pin "32") (pinfunction "VSS2_32") (pintype "bidirectional"))
      (node (ref "U10") (pin "1") (pinfunction "GND_1") (pintype "power_in"))
      (node (ref "U11") (pin "1") (pinfunction "GND_1") (pintype "power_in"))
      (node (ref "U12") (pin "1") (pinfunction "GND_1") (pintype "power_in"))
      (node (ref "U13") (pin "1") (pinfunction "GND_1") (pintype "power_in"))
      (node (ref "U20") (pin "1") (pinfunction "A0_1") (pintype "bidirectional"))
      (node (ref "U20") (pin "2") (pinfunction "A1_2") (pintype "bidirectional"))
      (node (ref "U20") (pin "3") (pinfunction "A2_3") (pintype "bidirectional"))
      (node (ref "U20") (pin "4") (pinfunction "VSS_4") (pintype "power_in"))
      (node (ref "U20") (pin "7") (pinfunction "WP_7") (pintype "bidirectional"))
      (node (ref "U21") (pin "1") (pinfunction "A0_1") (pintype "bidirectional"))
      (node (ref "U21") (pin "2") (pinfunction "A1_2") (pintype "bidirectional"))
      (node (ref "U21") (pin "4") (pinfunction "VSS_4") (pintype "power_in"))
      (node (ref "U21") (pin "7") (pinfunction "WP_7") (pintype "bidirectional"))
      (node (ref "U30") (pin "5") (pinfunction "GND_5") (pintype "bidirectional"))
      (node (ref "U31") (pin "5") (pinfunction "GND_5") (pintype "bidirectional"))
      (node (ref "U40") (pin "2") (pinfunction "GND_2") (pintype "bidirectional"))
      (node (ref "U70") (pin "1") (pinfunction "GND_1") (pintype "power_in"))
    )
    (net (code "43") (name "Net-(C3-Pad1)") (class "Default")
      (node (ref "C3") (pin "1") (pinfunction "1_1") (pintype "passive"))
      (node (ref "R1") (pin "1") (pinfunction "1_1") (pintype "passive"))
      (node (ref "Y1") (pin "1") (pinfunction "1_1") (pintype "passive"))
    )
    (net (code "44") (name "Net-(C4-Pad1)") (class "Default")
      (node (ref "C4") (pin "1") (pinfunction "1_1") (pintype "passive"))
      (node (ref "R19") (pin "1") (pinfunction "1_1") (pintype "passive"))
      (node (ref "Y1") (pin "2") (pinfunction "2_2") (pintype "passive"))
    )
    (net (code "45") (name "Net-(D1-PadA)") (class "Default")
      (node (ref "D1") (pin "A") (pinfunction "A_A") (pintype "passive"))
      (node (ref "R53") (pin "2") (pinfunction "2_2") (pintype "passive"))
    )
    (net (code "46") (name "Net-(D2-PadA)") (class "Default")
      (node (ref "D2") (pin "A") (pinfunction "A_A") (pintype "passive"))
      (node (ref "R54") (pin "2") (pinfunction "2_2") (pintype "passive"))
    )
    (net (code "47") (name "Net-(FB1-P$1)") (class "Default")
      (node (ref "FB1") (pin "1") (pinfunction "P$1_1") (pintype "passive"))
      (node (ref "J10") (pin "1") (pinfunction "1_1") (pintype "passive"))
    )
    (net (code "48") (name "Net-(FB1-P$2)") (class "Default")
      (node (ref "C14") (pin "1") (pinfunction "1_1") (pintype "passive"))
      (node (ref "FB1") (pin "2") (pinfunction "P$2_2") (pintype "passive"))
      (node (ref "U10") (pin "2") (pinfunction "T-_2") (pintype "input"))
    )
    (net (code "49") (name "Net-(FB2-P$1)") (class "Default")
      (node (ref "FB2") (pin "1") (pinfunction "P$1_1") (pintype "passive"))
      (node (ref "J10") (pin "2") (pinfunction "2_2") (pintype "passive"))
    )
    (net (code "50") (name "Net-(FB2-P$2)") (class "Default")
      (node (ref "C14") (pin "2") (pinfunction "2_2") (pintype "passive"))
      (node (ref "FB2") (pin "2") (pinfunction "P$2_2") (pintype "passive"))
      (node (ref "U10") (pin "3") (pinfunction "T+_3") (pintype "input"))
    )
    (net (code "51") (name "Net-(FB3-P$1)") (class "Default")
      (node (ref "FB3") (pin "1") (pinfunction "P$1_1") (pintype "passive"))
      (node (ref "J11") (pin "1") (pinfunction "1_1") (pintype "passive"))
    )
    (net (code "52") (name "Net-(FB3-P$2)") (class "Default")
      (node (ref "C15") (pin "1") (pinfunction "1_1") (pintype "passive"))
      (node (ref "FB3") (pin "2") (pinfunction "P$2_2") (pintype "passive"))
      (node (ref "U11") (pin "2") (pinfunction "T-_2") (pintype "input"))
    )
    (net (code "53") (name "Net-(FB4-P$1)") (class "Default")
      (node (ref "FB4") (pin "1") (pinfunction "P$1_1") (pintype "passive"))
      (node (ref "J11") (pin "2") (pinfunction "2_2") (pintype "passive"))
    )
    (net (code "54") (name "Net-(FB4-P$2)") (class "Default")
      (node (ref "C15") (pin "2") (pinfunction "2_2") (pintype "passive"))
      (node (ref "FB4") (pin "2") (pinfunction "P$2_2") (pintype "passive"))
      (node (ref "U11") (pin "3") (pinfunction "T+_3") (pintype "input"))
    )
    (net (code "55") (name "Net-(FB5-P$1)") (class "Default")
      (node (ref "FB5") (pin "1") (pinfunction "P$1_1") (pintype "passive"))
      (node (ref "J12") (pin "1") (pinfunction "1_1") (pintype "passive"))
    )
    (net (code "56") (name "Net-(FB5-P$2)") (class "Default")
      (node (ref "C16") (pin "1") (pinfunction "1_1") (pintype "passive"))
      (node (ref "FB5") (pin "2") (pinfunction "P$2_2") (pintype "passive"))
      (node (ref "U12") (pin "2") (pinfunction "T-_2") (pintype "input"))
    )
    (net (code "57") (name "Net-(FB6-P$1)") (class "Default")
      (node (ref "FB6") (pin "1") (pinfunction "P$1_1") (pintype "passive"))
      (node (ref "J12") (pin "2") (pinfunction "2_2") (pintype "passive"))
    )
    (net (code "58") (name "Net-(FB6-P$2)") (class "Default")
      (node (ref "C16") (pin "2") (pinfunction "2_2") (pintype "passive"))
      (node (ref "FB6") (pin "2") (pinfunction "P$2_2") (pintype "passive"))
      (node (ref "U12") (pin "3") (pinfunction "T+_3") (pintype "input"))
    )
    (net (code "59") (name "Net-(FB7-P$1)") (class "Default")
      (node (ref "FB7") (pin "1") (pinfunction "P$1_1") (pintype "passive"))
      (node (ref "J13") (pin "1") (pinfunction "1_1") (pintype "passive"))
    )
    (net (code "60") (name "Net-(FB7-P$2)") (class "Default")
      (node (ref "C17") (pin "1") (pinfunction "1_1") (pintype "passive"))
      (node (ref "FB7") (pin "2") (pinfunction "P$2_2") (pintype "passive"))
      (node (ref "U13") (pin "2") (pinfunction "T-_2") (pintype "input"))
    )
    (net (code "61") (name "Net-(FB8-P$1)") (class "Default")
      (node (ref "FB8") (pin "1") (pinfunction "P$1_1") (pintype "passive"))
      (node (ref "J13") (pin "2") (pinfunction "2_2") (pintype "passive"))
    )
    (net (code "62") (name "Net-(FB8-P$2)") (class "Default")
      (node (ref "C17") (pin "2") (pinfunction "2_2") (pintype "passive"))
      (node (ref "FB8") (pin "2") (pinfunction "P$2_2") (pintype "passive"))
      (node (ref "U13") (pin "3") (pinfunction "T+_3") (pintype "input"))
    )
    (net (code "63") (name "Net-(U1-PF0{slash}OSC_IN)") (class "Default")
      (node (ref "R1") (pin "2") (pinfunction "2_2") (pintype "passive"))
      (node (ref "U1") (pin "2") (pinfunction "PF0/OSC_IN_2") (pintype "bidirectional"))
    )
    (net (code "64") (name "Net-(U1-PF1{slash}OSC_OUT)") (class "Default")
      (node (ref "R19") (pin "2") (pinfunction "2_2") (pintype "passive"))
      (node (ref "U1") (pin "3") (pinfunction "PF1/OSC_OUT_3") (pintype "bidirectional"))
    )
    (net (code "65") (name "Net-(U40-EN)") (class "Default")
      (node (ref "C40") (pin "1") (pinfunction "1_1") (pintype "passive"))
      (node (ref "D3") (pin "C") (pinfunction "C_C") (pintype "passive"))
      (node (ref "U40") (pin "1") (pinfunction "VIN_1") (pintype "bidirectional"))
      (node (ref "U40") (pin "3") (pinfunction "EN_3") (pintype "bidirectional"))
    )
    (net (code "66") (name "unconnected-(J4-PadRING_SW)") (class "Default")
      (node (ref "J4") (pin "RING_SW") (pinfunction "RING_SW_RING_SW") (pintype "bidirectional"))
    )
    (net (code "67") (name "unconnected-(J7-Pad2)") (class "Default")
      (node (ref "J7") (pin "2") (pinfunction "2_2") (pintype "passive"))
    )
    (net (code "68") (name "unconnected-(J7-Pad6)") (class "Default")
      (node (ref "J7") (pin "6") (pinfunction "6_6") (pintype "passive"))
    )
    (net (code "69") (name "unconnected-(U40-BYP-Pad4)") (class "Default")
      (node (ref "U40") (pin "4") (pinfunction "BYP_4") (pintype "bidirectional"))
    )
  )
)
